# 08-LogicNAND.net
KiCad netlist of a schematic drawn in Altium Designer
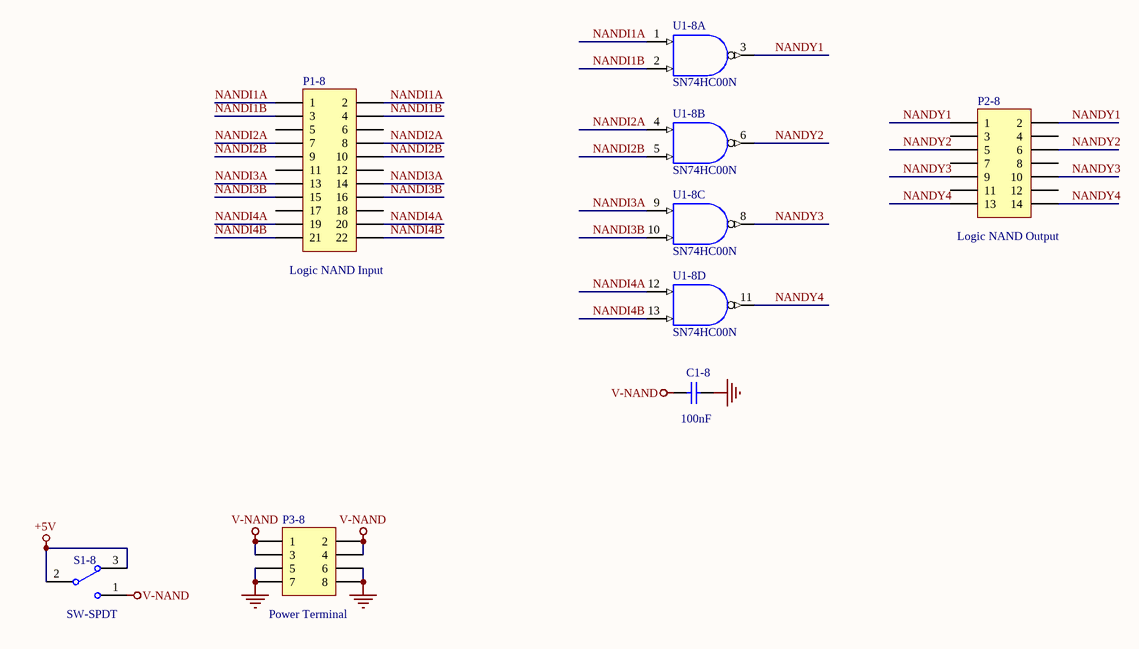
[diagram p0: 08-LogicNAND.SchDoc]

(export (version "E")
  (design (tool "Eeschema 10.0.6"))
  (components
    (comp (ref "C1-8")
      (value "100nF")
      (footprint "c-0805")
      (description "Capacitor")
      (fields (field (name "Comment") "104") (field (name "PUBLISHER") "Altium Limited"))
      (libsource (lib "Miscellaneous Devices") (part "Cap"))
    )
    (comp (ref "P1-8")
      (value "Logic NAND Input")
      (footprint "JP2.54-F-2x11A")
      (description "Header, 11-Pin, Dual row")
      (fields (field (name "Comment") "Header 11X2"))
      (libsource (lib "Miscellaneous Connectors") (part "Header 11X2"))
    )
    (comp (ref "P2-8")
      (value "Logic NAND Output")
      (footprint "JP2.54-F-2x07A")
      (description "Header, 7-Pin, Dual row")
      (fields (field (name "Comment") "H7X2"))
      (libsource (lib "Miscellaneous Connectors") (part "Header 7X2"))
    )
    (comp (ref "P3-8")
      (value "Header 4X2")
      (footprint "JP2.54-F-2x04A")
      (description "Header, 4-Pin, Dual row")
      (fields (field (name "PUBLISHER") "Power Terminal"))
      (libsource (lib "Miscellaneous Connectors") (part "Header 4X2"))
    )
    (comp (ref "S1-8")
      (value "SW-SPDT")
      (footprint "SW-SLIDE-2P-2W")
      (description "SPDT Subminiature Toggle Switch, Right Angle Mounting, Vertical Actuation")
      (fields (field (name "PUBLISHER") "Altium Limited"))
      (libsource (lib "Miscellaneous Devices") (part "SW-SPDT"))
    )
    (comp (ref "U1-8")
      (value "SN74HC00N")
      (footprint "SK-DIP14-300")
      (description "Quadruple 2-Input Positive-NAND Gate")
      (fields (field (name "PUBLISHER") "Altium Limited"))
      (libsource (lib "TI Logic Gate 2") (part "SN74HC00N"))
    )
  )
  (nets
    (net (code "1") (name "+5V") (class "Default")
      (node (ref "S1-8") (pin "2") (pinfunction "2_2") (pintype "passive"))
      (node (ref "S1-8") (pin "3") (pinfunction "3_3") (pintype "passive"))
    )
    (net (code "2") (name "/NANDI1A") (class "Default")
      (node (ref "P1-8") (pin "1") (pinfunction "1_1") (pintype "passive"))
      (node (ref "P1-8") (pin "2") (pinfunction "2_2") (pintype "passive"))
      (node (ref "U1-8") (pin "1") (pinfunction "A_1") (pintype "input"))
    )
    (net (code "3") (name "/NANDI1B") (class "Default")
      (node (ref "P1-8") (pin "3") (pinfunction "3_3") (pintype "passive"))
      (node (ref "P1-8") (pin "4") (pinfunction "4_4") (pintype "passive"))
      (node (ref "U1-8") (pin "2") (pinfunction "B_2") (pintype "input"))
    )
    (net (code "4") (name "/NANDI2A") (class "Default")
      (node (ref "P1-8") (pin "7") (pinfunction "7_7") (pintype "passive"))
      (node (ref "P1-8") (pin "8") (pinfunction "8_8") (pintype "passive"))
      (node (ref "U1-8") (pin "4") (pinfunction "A_4") (pintype "input"))
    )
    (net (code "5") (name "/NANDI2B") (class "Default")
      (node (ref "P1-8") (pin "10") (pinfunction "10_10") (pintype "passive"))
      (node (ref "P1-8") (pin "9") (pinfunction "9_9") (pintype "passive"))
      (node (ref "U1-8") (pin "5") (pinfunction "B_5") (pintype "input"))
    )
    (net (code "6") (name "/NANDI3A") (class "Default")
      (node (ref "P1-8") (pin "13") (pinfunction "13_13") (pintype "passive"))
      (node (ref "P1-8") (pin "14") (pinfunction "14_14") (pintype "passive"))
      (node (ref "U1-8") (pin "9") (pinfunction "A_9") (pintype "input"))
    )
    (net (code "7") (name "/NANDI3B") (class "Default")
      (node (ref "P1-8") (pin "15") (pinfunction "15_15") (pintype "passive"))
      (node (ref "P1-8") (pin "16") (pinfunction "16_16") (pintype "passive"))
      (node (ref "U1-8") (pin "10") (pinfunction "B_10") (pintype "input"))
    )
    (net (code "8") (name "/NANDI4A") (class "Default")
      (node (ref "P1-8") (pin "19") (pinfunction "19_19") (pintype "passive"))
      (node (ref "P1-8") (pin "20") (pinfunction "20_20") (pintype "passive"))
      (node (ref "U1-8") (pin "12") (pinfunction "A_12") (pintype "input"))
    )
    (net (code "9") (name "/NANDI4B") (class "Default")
      (node (ref "P1-8") (pin "21") (pinfunction "21_21") (pintype "passive"))
      (node (ref "P1-8") (pin "22") (pinfunction "22_22") (pintype "passive"))
      (node (ref "U1-8") (pin "13") (pinfunction "B_13") (pintype "input"))
    )
    (net (code "10") (name "/NANDY1") (class "Default")
      (node (ref "P2-8") (pin "1") (pinfunction "1_1") (pintype "passive"))
      (node (ref "P2-8") (pin "2") (pinfunction "2_2") (pintype "passive"))
      (node (ref "U1-8") (pin "3") (pinfunction "Y_3") (pintype "output"))
    )
    (net (code "11") (name "/NANDY2") (class "Default")
      (node (ref "P2-8") (pin "5") (pinfunction "5_5") (pintype "passive"))
      (node (ref "P2-8") (pin "6") (pinfunction "6_6") (pintype "passive"))
      (node (ref "U1-8") (pin "6") (pinfunction "Y_6") (pintype "output"))
    )
    (net (code "12") (name "/NANDY3") (class "Default")
      (node (ref "P2-8") (pin "10") (pinfunction "10_10") (pintype "passive"))
      (node (ref "P2-8") (pin "9") (pinfunction "9_9") (pintype "passive"))
      (node (ref "U1-8") (pin "8") (pinfunction "Y_8") (pintype "output"))
    )
    (net (code "13") (name "/NANDY4") (class "Default")
      (node (ref "P2-8") (pin "13") (pinfunction "13_13") (pintype "passive"))
      (node (ref "P2-8") (pin "14") (pinfunction "14_14") (pintype "passive"))
      (node (ref "U1-8") (pin "11") (pinfunction "Y_11") (pintype "output"))
    )
    (net (code "14") (name "GND") (class "Default")
      (node (ref "C1-8") (pin "2") (pinfunction "2_2") (pintype "passive"))
      (node (ref "P3-8") (pin "5") (pinfunction "5_5") (pintype "passive"))
      (node (ref "P3-8") (pin "6") (pinfunction "6_6") (pintype "passive"))
      (node (ref "P3-8") (pin "7") (pinfunction "7_7") (pintype "passive"))
      (node (ref "P3-8") (pin "8") (pinfunction "8_8") (pintype "passive"))
      (node (ref "U1-8") (pin "7") (pinfunction "GND_7") (pintype "power_in"))
    )
    (net (code "15") (name "V-NAND") (class "Default")
      (node (ref "C1-8") (pin "1") (pinfunction "1_1") (pintype "passive"))
      (node (ref "P3-8") (pin "1") (pinfunction "1_1") (pintype "passive"))
      (node (ref "P3-8") (pin "2") (pinfunction "2_2") (pintype "passive"))
      (node (ref "P3-8") (pin "3") (pinfunction "3_3") (pintype "passive"))
      (node (ref "P3-8") (pin "4") (pinfunction "4_4") (pintype "passive"))
      (node (ref "S1-8") (pin "1") (pinfunction "1_1") (pintype "passive"))
      (node (ref "U1-8") (pin "14") (pinfunction "V-NAND_14") (pintype "power_in"))
    )
    (net (code "16") (name "unconnected-(P1-8-Pad5)") (class "Default")
      (node (ref "P1-8") (pin "5") (pinfunction "5_5") (pintype "passive"))
    )
    (net (code "17") (name "unconnected-(P1-8-Pad6)") (class "Default")
      (node (ref "P1-8") (pin "6") (pinfunction "6_6") (pintype "passive"))
    )
    (net (code "18") (name "unconnected-(P1-8-Pad11)") (class "Default")
      (node (ref "P1-8") (pin "11") (pinfunction "11_11") (pintype "passive"))
    )
    (net (code "19") (name "unconnected-(P1-8-Pad12)") (class "Default")
      (node (ref "P1-8") (pin "12") (pinfunction "12_12") (pintype "passive"))
    )
    (net (code "20") (name "unconnected-(P1-8-Pad17)") (class "Default")
      (node (ref "P1-8") (pin "17") (pinfunction "17_17") (pintype "passive"))
    )
    (net (code "21") (name "unconnected-(P1-8-Pad18)") (class "Default")
      (node (ref "P1-8") (pin "18") (pinfunction "18_18") (pintype "passive"))
    )
    (net (code "22") (name "unconnected-(P2-8-Pad3)") (class "Default")
      (node (ref "P2-8") (pin "3") (pinfunction "3_3") (pintype "passive"))
    )
    (net (code "23") (name "unconnected-(P2-8-Pad4)") (class "Default")
      (node (ref "P2-8") (pin "4") (pinfunction "4_4") (pintype "passive"))
    )
    (net (code "24") (name "unconnected-(P2-8-Pad7)") (class "Default")
      (node (ref "P2-8") (pin "7") (pinfunction "7_7") (pintype "passive"))
    )
    (net (code "25") (name "unconnected-(P2-8-Pad8)") (class "Default")
      (node (ref "P2-8") (pin "8") (pinfunction "8_8") (pintype "passive"))
    )
    (net (code "26") (name "unconnected-(P2-8-Pad11)") (class "Default")
      (node (ref "P2-8") (pin "11") (pinfunction "11_11") (pintype "passive"))
    )
    (net (code "27") (name "unconnected-(P2-8-Pad12)") (class "Default")
      (node (ref "P2-8") (pin "12") (pinfunction "12_12") (pintype "passive"))
    )
  )
)
